# ATRACK_PILOT_V1.net
KiCad netlist of a schematic drawn in Altium Designer
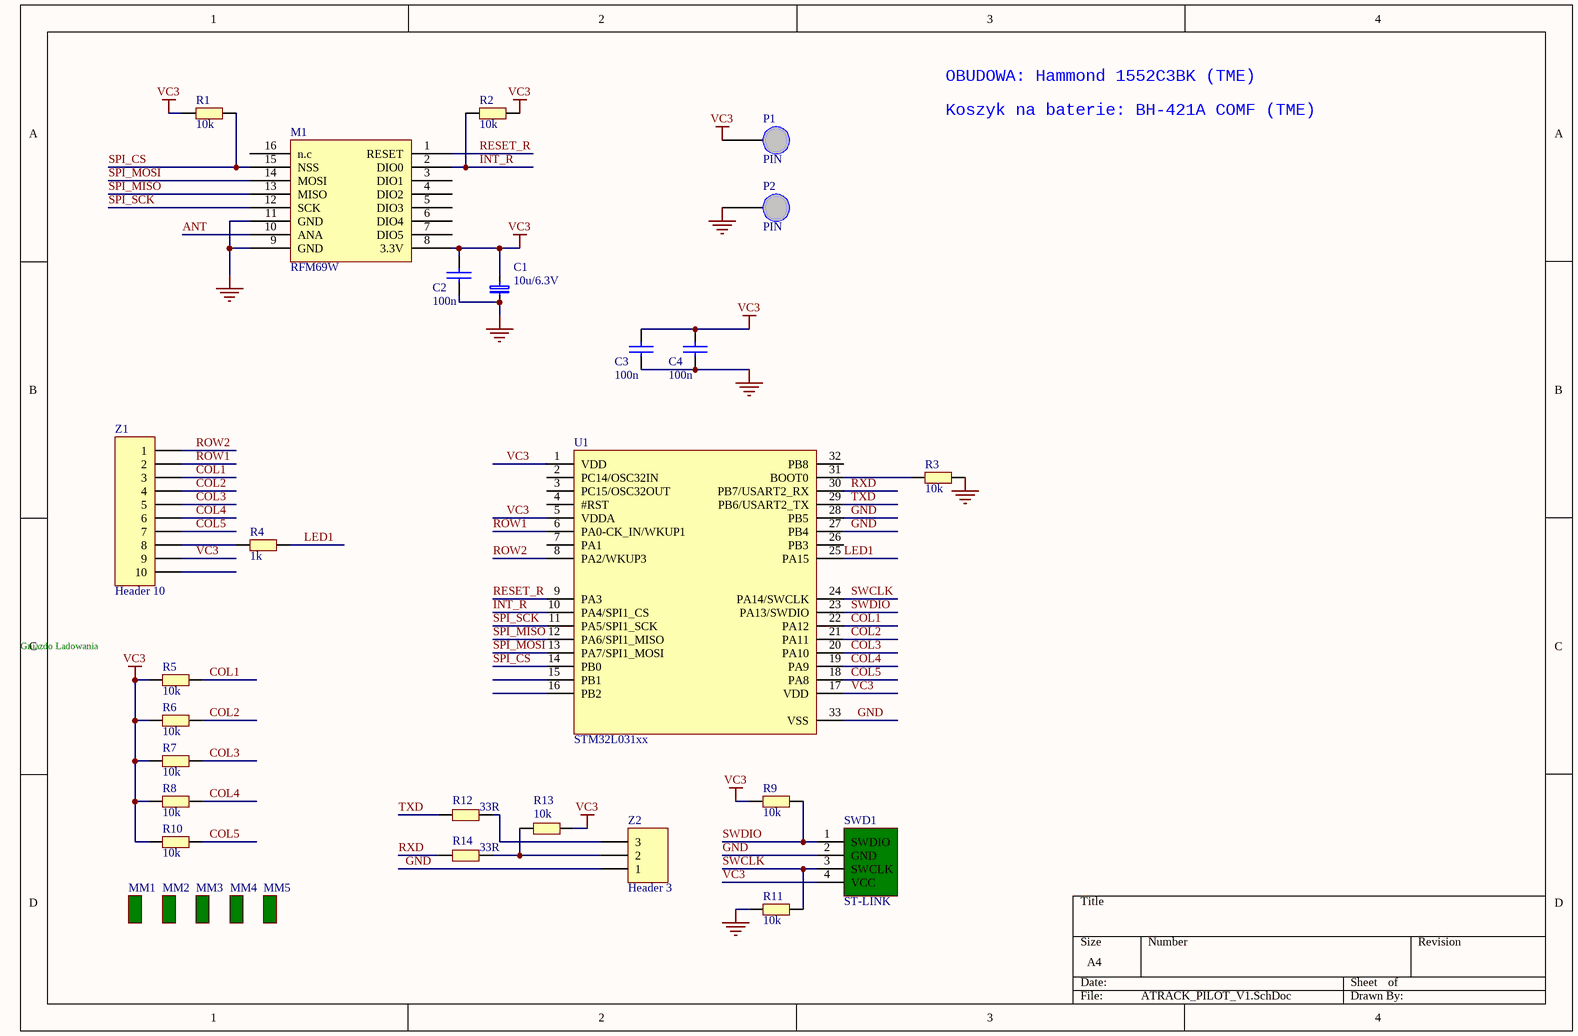
[diagram p0: ATRACK_PILOT_V1.SchDoc]

(export (version "E")
  (design (tool "Eeschema 10.0.6"))
  (components
    (comp (ref "C1")
      (value "10u/6.3V")
      (footprint "CAP_A")
      (description "KONDENSATOR ELEKTROLITYCZNY TANTALOWY SMD")
      (libsource (lib "*") (part "CAP_TANTAL_SMD"))
    )
    (comp (ref "C2")
      (value "100n")
      (footprint "0603C")
      (description "Capacitor")
      (libsource (lib "*") (part "CAP"))
    )
    (comp (ref "C3")
      (value "100n")
      (footprint "0603C")
      (description "Capacitor")
      (libsource (lib "*") (part "CAP"))
    )
    (comp (ref "C4")
      (value "100n")
      (footprint "0603C")
      (description "Capacitor")
      (libsource (lib "*") (part "CAP"))
    )
    (comp (ref "M1") (value "RFM69W") (footprint "RFM69W") (libsource (lib "GkSchlib") (part "RFM96W")))
    (comp (ref "MM1") (value "~") (footprint "REF_CIR") (libsource (lib "*") (part "MECH")))
    (comp (ref "MM2") (value "~") (footprint "REF_CIR") (libsource (lib "*") (part "MECH")))
    (comp (ref "MM3") (value "~") (footprint "REF_SQR") (libsource (lib "*") (part "MECH")))
    (comp (ref "MM4") (value "~") (footprint "REF_SQR") (libsource (lib "*") (part "MECH")))
    (comp (ref "MM5") (value "~") (footprint "PB_FREE_GRAF") (libsource (lib "*") (part "MECH")))
    (comp (ref "P1") (value "PIN") (footprint "PP_PICO6") (libsource (lib "GkSchlib") (part "PIN")))
    (comp (ref "P2") (value "PIN") (footprint "PP_PICO6") (libsource (lib "GkSchlib") (part "PIN")))
    (comp (ref "R1") (value "10k") (footprint "0603R") (libsource (lib "*") (part "RES3")))
    (comp (ref "R2") (value "10k") (footprint "0603R") (libsource (lib "*") (part "RES3")))
    (comp (ref "R3") (value "10k") (footprint "0603R") (libsource (lib "*") (part "RES3")))
    (comp (ref "R4") (value "1k") (footprint "0603R") (libsource (lib "*") (part "RES3")))
    (comp (ref "R5") (value "10k") (footprint "0603R") (libsource (lib "") (part "RES3_1")))
    (comp (ref "R6") (value "10k") (footprint "0603R") (libsource (lib "") (part "RES3_1")))
    (comp (ref "R7") (value "10k") (footprint "0603R") (libsource (lib "") (part "RES3_1")))
    (comp (ref "R8") (value "10k") (footprint "0603R") (libsource (lib "") (part "RES3_1")))
    (comp (ref "R9") (value "10k") (footprint "0603R") (libsource (lib "") (part "RES3_1")))
    (comp (ref "R10") (value "10k") (footprint "0603R") (libsource (lib "") (part "RES3_1")))
    (comp (ref "R11") (value "10k") (footprint "0603R") (libsource (lib "") (part "RES3_1")))
    (comp (ref "R12") (value "33R") (footprint "0603R") (libsource (lib "*") (part "RES3")))
    (comp (ref "R13") (value "10k") (footprint "0603R") (libsource (lib "") (part "RES3_1")))
    (comp (ref "R14") (value "33R") (footprint "0603R") (libsource (lib "*") (part "RES3")))
    (comp (ref "SWD1")
      (value "ST-LINK")
      (footprint "PIN4")
      (description "Header, 4-Pin")
      (fields (field (name "PUBLISHER") "Altium Limited"))
      (libsource (lib "GkSchlib") (part "SW_CON"))
    )
    (comp (ref "U1")
      (value "STM32L031xx")
      (footprint "UFQFPN32")
      (libsource (lib "GkSchlib") (part "STM32L031xx/UFQFPN32"))
    )
    (comp (ref "Z1")
      (value "Header 10")
      (footprint "MX-52271-2079")
      (description "Header, 10-Pin")
      (fields (field (name "PUBLISHER") "Altium Limited"))
      (libsource (lib "Miscellaneous Connectors") (part "Header 10"))
    )
    (comp (ref "Z2")
      (value "Header 3")
      (footprint "PIN3")
      (description "Header, 3-Pin")
      (fields (field (name "PUBLISHER") "Altium Limited"))
      (libsource (lib "Miscellaneous Connectors") (part "Header 3"))
    )
  )
  (nets
    (net (code "1") (name "/ANT") (class "Default")
      (node (ref "M1") (pin "10") (pinfunction "ANA_10") (pintype "passive"))
    )
    (net (code "2") (name "/COL1") (class "Default")
      (node (ref "R5") (pin "2") (pintype "passive"))
      (node (ref "U1") (pin "22") (pinfunction "PA12_22") (pintype "passive"))
      (node (ref "Z1") (pin "3") (pinfunction "3_3") (pintype "passive"))
    )
    (net (code "3") (name "/COL2") (class "Default")
      (node (ref "R6") (pin "2") (pintype "passive"))
      (node (ref "U1") (pin "21") (pinfunction "PA11_21") (pintype "passive"))
      (node (ref "Z1") (pin "4") (pinfunction "4_4") (pintype "passive"))
    )
    (net (code "4") (name "/COL3") (class "Default")
      (node (ref "R7") (pin "2") (pintype "passive"))
      (node (ref "U1") (pin "20") (pinfunction "PA10_20") (pintype "passive"))
      (node (ref "Z1") (pin "5") (pinfunction "5_5") (pintype "passive"))
    )
    (net (code "5") (name "/COL4") (class "Default")
      (node (ref "R8") (pin "2") (pintype "passive"))
      (node (ref "U1") (pin "19") (pinfunction "PA9_19") (pintype "passive"))
      (node (ref "Z1") (pin "6") (pinfunction "6_6") (pintype "passive"))
    )
    (net (code "6") (name "/COL5") (class "Default")
      (node (ref "R10") (pin "2") (pintype "passive"))
      (node (ref "U1") (pin "18") (pinfunction "PA8_18") (pintype "passive"))
      (node (ref "Z1") (pin "7") (pinfunction "7_7") (pintype "passive"))
    )
    (net (code "7") (name "/INT_R") (class "Default")
      (node (ref "M1") (pin "2") (pinfunction "DIO0_2") (pintype "passive"))
      (node (ref "R2") (pin "2") (pintype "passive"))
      (node (ref "U1") (pin "10") (pinfunction "PA4/SPI1_CS_10") (pintype "passive"))
    )
    (net (code "8") (name "/LED1") (class "Default")
      (node (ref "R4") (pin "1") (pintype "passive"))
      (node (ref "U1") (pin "25") (pinfunction "PA15_25") (pintype "passive"))
    )
    (net (code "9") (name "/RESET_R") (class "Default")
      (node (ref "M1") (pin "1") (pinfunction "RESET_1") (pintype "passive"))
      (node (ref "U1") (pin "9") (pinfunction "PA3_9") (pintype "passive"))
    )
    (net (code "10") (name "/ROW1") (class "Default")
      (node (ref "U1") (pin "6") (pinfunction "PA0-CK_IN/WKUP1_6") (pintype "passive"))
      (node (ref "Z1") (pin "2") (pinfunction "2_2") (pintype "passive"))
    )
    (net (code "11") (name "/ROW2") (class "Default")
      (node (ref "U1") (pin "8") (pinfunction "PA2/WKUP3_8") (pintype "passive"))
      (node (ref "Z1") (pin "1") (pinfunction "1_1") (pintype "passive"))
    )
    (net (code "12") (name "/RXD") (class "Default")
      (node (ref "R14") (pin "2") (pintype "passive"))
      (node (ref "U1") (pin "30") (pinfunction "PB7/USART2_RX_30") (pintype "passive"))
    )
    (net (code "13") (name "/SPI_CS") (class "Default")
      (node (ref "M1") (pin "15") (pinfunction "NSS_15") (pintype "passive"))
      (node (ref "R1") (pin "1") (pintype "passive"))
      (node (ref "U1") (pin "14") (pinfunction "PB0_14") (pintype "passive"))
    )
    (net (code "14") (name "/SPI_MISO") (class "Default")
      (node (ref "M1") (pin "13") (pinfunction "MISO_13") (pintype "passive"))
      (node (ref "U1") (pin "12") (pinfunction "PA6/SPI1_MISO_12") (pintype "passive"))
    )
    (net (code "15") (name "/SPI_MOSI") (class "Default")
      (node (ref "M1") (pin "14") (pinfunction "MOSI_14") (pintype "passive"))
      (node (ref "U1") (pin "13") (pinfunction "PA7/SPI1_MOSI_13") (pintype "passive"))
    )
    (net (code "16") (name "/SPI_SCK") (class "Default")
      (node (ref "M1") (pin "12") (pinfunction "SCK_12") (pintype "passive"))
      (node (ref "U1") (pin "11") (pinfunction "PA5/SPI1_SCK_11") (pintype "passive"))
    )
    (net (code "17") (name "/SWCLK") (class "Default")
      (node (ref "R11") (pin "2") (pintype "passive"))
      (node (ref "SWD1") (pin "3") (pinfunction "SWCLK_3") (pintype "passive"))
      (node (ref "U1") (pin "24") (pinfunction "PA14/SWCLK_24") (pintype "passive"))
    )
    (net (code "18") (name "/SWDIO") (class "Default")
      (node (ref "R9") (pin "2") (pintype "passive"))
      (node (ref "SWD1") (pin "1") (pinfunction "SWDIO_1") (pintype "passive"))
      (node (ref "U1") (pin "23") (pinfunction "PA13/SWDIO_23") (pintype "passive"))
    )
    (net (code "19") (name "/TXD") (class "Default")
      (node (ref "R12") (pin "2") (pintype "passive"))
      (node (ref "U1") (pin "29") (pinfunction "PB6/USART2_TX_29") (pintype "passive"))
    )
    (net (code "20") (name "GND") (class "Default")
      (node (ref "C1") (pin "1") (pintype "passive"))
      (node (ref "C2") (pin "1") (pinfunction "1_1") (pintype "passive"))
      (node (ref "C3") (pin "1") (pinfunction "1_1") (pintype "passive"))
      (node (ref "C4") (pin "1") (pinfunction "1_1") (pintype "passive"))
      (node (ref "M1") (pin "11") (pinfunction "GND_11") (pintype "passive"))
      (node (ref "M1") (pin "9") (pinfunction "GND_9") (pintype "passive"))
      (node (ref "P2") (pin "1") (pintype "passive"))
      (node (ref "R11") (pin "1") (pintype "passive"))
      (node (ref "R3") (pin "1") (pintype "passive"))
      (node (ref "SWD1") (pin "2") (pinfunction "GND_2") (pintype "passive"))
      (node (ref "U1") (pin "27") (pinfunction "PB4_27") (pintype "passive"))
      (node (ref "U1") (pin "28") (pinfunction "PB5_28") (pintype "passive"))
      (node (ref "U1") (pin "33") (pinfunction "VSS_33") (pintype "passive"))
      (node (ref "Z2") (pin "1") (pinfunction "1_1") (pintype "passive"))
    )
    (net (code "21") (name "Net-(R4-Pad2)") (class "Default")
      (node (ref "R4") (pin "2") (pintype "passive"))
      (node (ref "Z1") (pin "8") (pinfunction "8_8") (pintype "passive"))
    )
    (net (code "22") (name "Net-(R12-Pad1)") (class "Default")
      (node (ref "R12") (pin "1") (pintype "passive"))
      (node (ref "Z2") (pin "3") (pinfunction "3_3") (pintype "passive"))
    )
    (net (code "23") (name "Net-(R13-Pad1)") (class "Default")
      (node (ref "R13") (pin "1") (pintype "passive"))
      (node (ref "R14") (pin "1") (pintype "passive"))
      (node (ref "Z2") (pin "2") (pinfunction "2_2") (pintype "passive"))
    )
    (net (code "24") (name "Net-(U1-BOOT0)") (class "Default")
      (node (ref "R3") (pin "2") (pintype "passive"))
      (node (ref "U1") (pin "31") (pinfunction "BOOT0_31") (pintype "passive"))
    )
    (net (code "25") (name "VC3") (class "Default")
      (node (ref "C1") (pin "2") (pintype "passive"))
      (node (ref "C2") (pin "2") (pinfunction "2_2") (pintype "passive"))
      (node (ref "C3") (pin "2") (pinfunction "2_2") (pintype "passive"))
      (node (ref "C4") (pin "2") (pinfunction "2_2") (pintype "passive"))
      (node (ref "M1") (pin "8") (pinfunction "3.3V_8") (pintype "passive"))
      (node (ref "P1") (pin "1") (pintype "passive"))
      (node (ref "R1") (pin "2") (pintype "passive"))
      (node (ref "R10") (pin "1") (pintype "passive"))
      (node (ref "R13") (pin "2") (pintype "passive"))
      (node (ref "R2") (pin "1") (pintype "passive"))
      (node (ref "R5") (pin "1") (pintype "passive"))
      (node (ref "R6") (pin "1") (pintype "passive"))
      (node (ref "R7") (pin "1") (pintype "passive"))
      (node (ref "R8") (pin "1") (pintype "passive"))
      (node (ref "R9") (pin "1") (pintype "passive"))
      (node (ref "SWD1") (pin "4") (pinfunction "VCC_4") (pintype "passive"))
      (node (ref "U1") (pin "1") (pinfunction "VDD_1") (pintype "passive"))
      (node (ref "U1") (pin "17") (pinfunction "VDD_17") (pintype "passive"))
      (node (ref "U1") (pin "5") (pinfunction "VDDA_5") (pintype "passive"))
      (node (ref "Z1") (pin "9") (pinfunction "9_9") (pintype "passive"))
    )
    (net (code "26") (name "unconnected-(M1-DIO1-Pad3)") (class "Default")
      (node (ref "M1") (pin "3") (pinfunction "DIO1_3") (pintype "passive"))
    )
    (net (code "27") (name "unconnected-(M1-DIO2-Pad4)") (class "Default")
      (node (ref "M1") (pin "4") (pinfunction "DIO2_4") (pintype "passive"))
    )
    (net (code "28") (name "unconnected-(M1-DIO3-Pad5)") (class "Default")
      (node (ref "M1") (pin "5") (pinfunction "DIO3_5") (pintype "passive"))
    )
    (net (code "29") (name "unconnected-(M1-DIO4-Pad6)") (class "Default")
      (node (ref "M1") (pin "6") (pinfunction "DIO4_6") (pintype "passive"))
    )
    (net (code "30") (name "unconnected-(M1-DIO5-Pad7)") (class "Default")
      (node (ref "M1") (pin "7") (pinfunction "DIO5_7") (pintype "passive"))
    )
    (net (code "31") (name "unconnected-(M1-n.c-Pad16)") (class "Default")
      (node (ref "M1") (pin "16") (pinfunction "n.c_16") (pintype "passive"))
    )
    (net (code "32") (name "unconnected-(U1-#RST-Pad4)") (class "Default")
      (node (ref "U1") (pin "4") (pinfunction "#RST_4") (pintype "passive"))
    )
    (net (code "33") (name "unconnected-(U1-PA1-Pad7)") (class "Default")
      (node (ref "U1") (pin "7") (pinfunction "PA1_7") (pintype "passive"))
    )
    (net (code "34") (name "unconnected-(U1-PB1-Pad15)") (class "Default")
      (node (ref "U1") (pin "15") (pinfunction "PB1_15") (pintype "passive"))
    )
    (net (code "35") (name "unconnected-(U1-PB2-Pad16)") (class "Default")
      (node (ref "U1") (pin "16") (pinfunction "PB2_16") (pintype "passive"))
    )
    (net (code "36") (name "unconnected-(U1-PB3-Pad26)") (class "Default")
      (node (ref "U1") (pin "26") (pinfunction "PB3_26") (pintype "passive"))
    )
    (net (code "37") (name "unconnected-(U1-PB8-Pad32)") (class "Default")
      (node (ref "U1") (pin "32") (pinfunction "PB8_32") (pintype "passive"))
    )
    (net (code "38") (name "unconnected-(U1-PC14{slash}OSC32IN-Pad2)") (class "Default")
      (node (ref "U1") (pin "2") (pinfunction "PC14/OSC32IN_2") (pintype "passive"))
    )
    (net (code "39") (name "unconnected-(U1-PC15{slash}OSC32OUT-Pad3)") (class "Default")
      (node (ref "U1") (pin "3") (pinfunction "PC15/OSC32OUT_3") (pintype "passive"))
    )
    (net (code "40") (name "unconnected-(Z1-Pad10)") (class "Default")
      (node (ref "Z1") (pin "10") (pinfunction "10_10") (pintype "passive"))
    )
  )
)
